# Sensors.net
KiCad netlist of a schematic drawn in Altium Designer
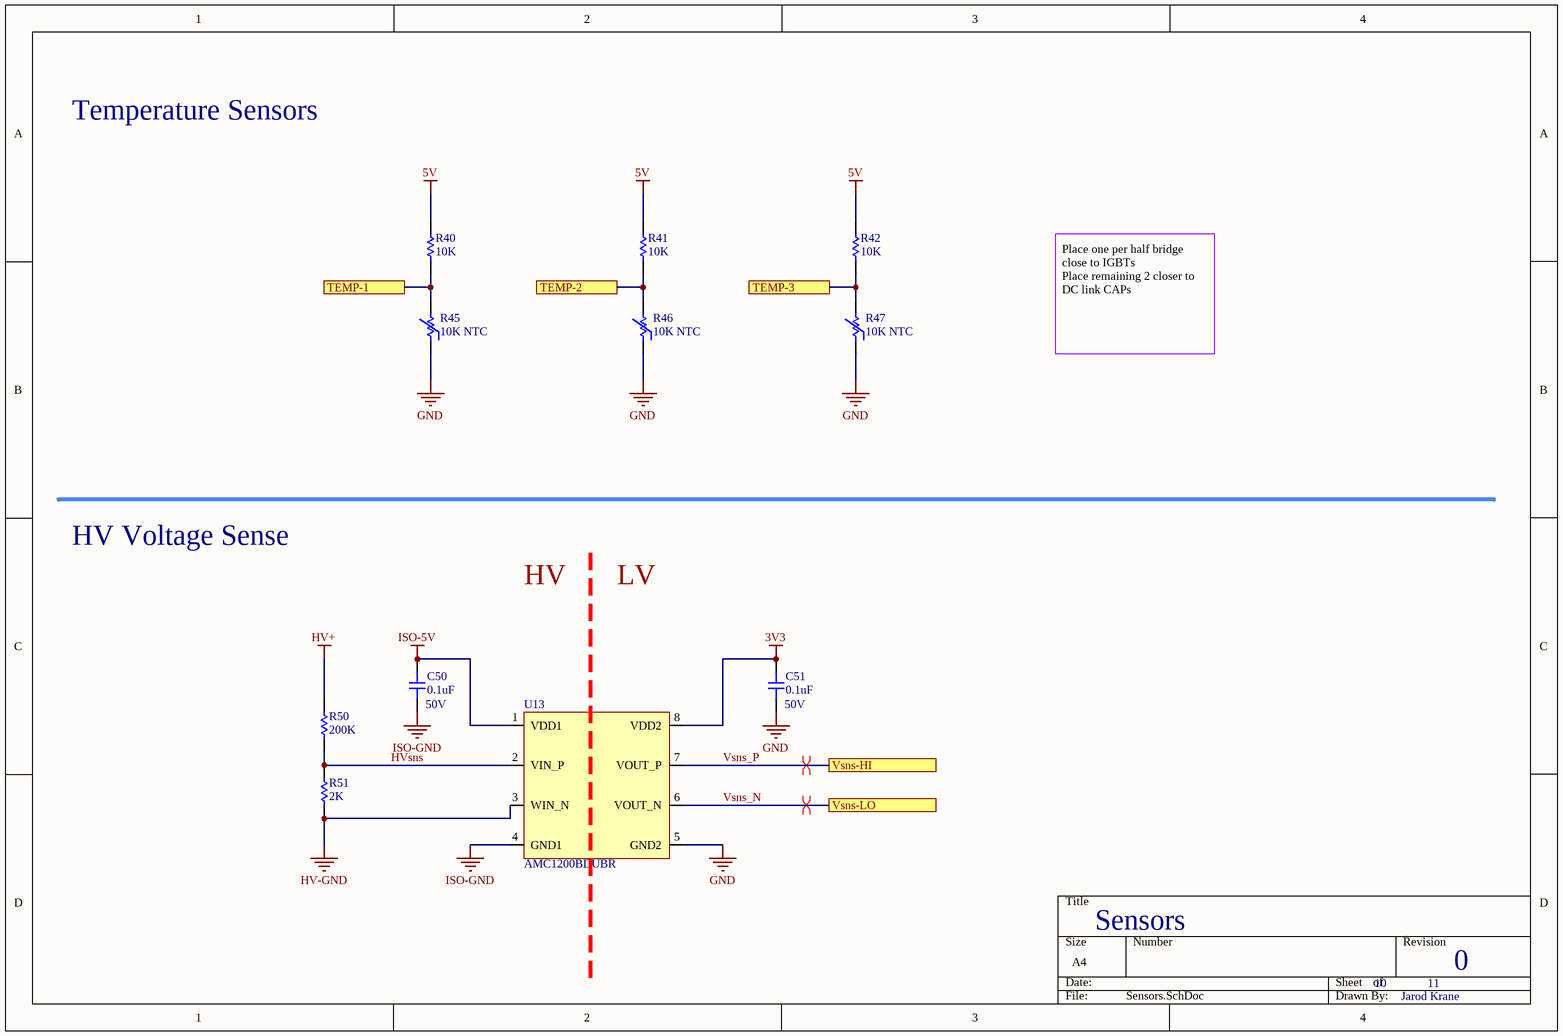
[diagram p0: Sensors.SchDoc]

(export (version "E")
  (design (tool "Eeschema 10.0.6"))
  (components
    (comp (ref "C50")
      (value "0.1uF")
      (footprint "CAP-0805")
      (description "CAP CER 0.1UF 50V Y5V 0805")
      (fields
        (field (name "MANUFACTURER") "KEMET")
        (field (name "MANUFACTURER PART NUMBER") "C0805C104Z5VACTU")
        (field (name "VOLTAGE RATING (DC)") "50V")
      )
      (libsource (lib "InverterSCHLib") (part "0805-0.1uF-50V"))
    )
    (comp (ref "C51")
      (value "0.1uF")
      (footprint "CAP-0805")
      (description "CAP CER 0.1UF 50V Y5V 0805")
      (fields
        (field (name "MANUFACTURER") "KEMET")
        (field (name "MANUFACTURER PART NUMBER") "C0805C104Z5VACTU")
        (field (name "VOLTAGE") "50V")
      )
      (libsource (lib "InverterSCHLib") (part "0805-0.1uF-50V"))
    )
    (comp (ref "R40")
      (value "10K")
      (footprint "RES-0603")
      (description "RES SMD 10K OHM 5% 1/10W 0603")
      (fields
        (field (name "MANUFACTURER") "Yageo")
        (field (name "MANUFACTURER PART NUMBER") "RC0603JR-0710KL")
      )
      (libsource (lib "InverterSCHLib") (part "0603-10KR"))
    )
    (comp (ref "R41")
      (value "10K")
      (footprint "RES-0603")
      (description "RES SMD 10K OHM 5% 1/10W 0603")
      (fields
        (field (name "MANUFACTURER") "Yageo")
        (field (name "MANUFACTURER PART NUMBER") "RC0603JR-0710KL")
      )
      (libsource (lib "InverterSCHLib") (part "0603-10KR"))
    )
    (comp (ref "R42")
      (value "10K")
      (footprint "RES-0603")
      (description "RES SMD 10K OHM 5% 1/10W 0603")
      (fields
        (field (name "MANUFACTURER") "Yageo")
        (field (name "MANUFACTURER PART NUMBER") "RC0603JR-0710KL")
      )
      (libsource (lib "InverterSCHLib") (part "0603-10KR"))
    )
    (comp (ref "R45")
      (value "10K NTC")
      (footprint "RES-0603")
      (description "THERMISTOR NTC 10KOHM 3380K 0603")
      (fields
        (field (name "MANUFACTURER") "Murata")
        (field (name "MANUFACTURER PART NUMBER") "NCP18XH103F03RB")
      )
      (libsource (lib "InverterSCHLib") (part "0603-10K-thermistor"))
    )
    (comp (ref "R46")
      (value "10K NTC")
      (footprint "RES-0603")
      (description "THERMISTOR NTC 10KOHM 3380K 0603")
      (fields
        (field (name "MANUFACTURER") "Murata")
        (field (name "MANUFACTURER PART NUMBER") "NCP18XH103F03RB")
      )
      (libsource (lib "InverterSCHLib") (part "0603-10K-thermistor"))
    )
    (comp (ref "R47")
      (value "10K NTC")
      (footprint "RES-0603")
      (description "THERMISTOR NTC 10KOHM 3380K 0603")
      (fields
        (field (name "MANUFACTURER") "Murata")
        (field (name "MANUFACTURER PART NUMBER") "NCP18XH103F03RB")
      )
      (libsource (lib "InverterSCHLib") (part "0603-10K-thermistor"))
    )
    (comp (ref "R50")
      (value "200K")
      (footprint "RES-0603")
      (description "RES SMD 200K OHM 1% 1/10W 0603")
      (fields
        (field (name "MANUFACTURER") "Yageo")
        (field (name "MANUFACTURER PART NUMBER") "AF0603FR-07200KL")
      )
      (libsource (lib "InverterSCHLib") (part "0603-200KR"))
    )
    (comp (ref "R51")
      (value "2K")
      (footprint "RES-0603")
      (description "RES SMD 2K OHM 1% 1/4W 0603")
      (fields
        (field (name "MANUFACTURER") "Vishay Dale")
        (field (name "MANUFACTURER PART NUMBER") "CRCW06032K00FKEAHP")
      )
      (libsource (lib "InverterSCHLib") (part "0603-2KR"))
    )
    (comp (ref "U13")
      (value "AMC1200BDUBR")
      (footprint "8-SOP")
      (description "IC OPAMP ISOLATION 1 CIRC 8SOP")
      (fields (field (name "MANUFACTURER") "Texas Instruments"))
      (libsource (lib "InverterSCHLib") (part "ISO-OPAMP"))
    )
  )
  (nets
    (net (code "1") (name "/HVsns") (class "Default")
      (node (ref "R50") (pin "1") (pinfunction "1_1") (pintype "passive"))
      (node (ref "R51") (pin "2") (pinfunction "2_2") (pintype "passive"))
      (node (ref "U13") (pin "2") (pinfunction "VIN_P_2") (pintype "passive"))
    )
    (net (code "2") (name "/TEMP-1") (class "Default")
      (node (ref "R40") (pin "1") (pinfunction "1_1") (pintype "passive"))
      (node (ref "R45") (pin "2") (pinfunction "2_2") (pintype "passive"))
    )
    (net (code "3") (name "/TEMP-2") (class "Default")
      (node (ref "R41") (pin "1") (pinfunction "1_1") (pintype "passive"))
      (node (ref "R46") (pin "2") (pinfunction "2_2") (pintype "passive"))
    )
    (net (code "4") (name "/TEMP-3") (class "Default")
      (node (ref "R42") (pin "1") (pinfunction "1_1") (pintype "passive"))
      (node (ref "R47") (pin "2") (pinfunction "2_2") (pintype "passive"))
    )
    (net (code "5") (name "/Vsns_N") (class "Default")
      (node (ref "U13") (pin "6") (pinfunction "VOUT_N_6") (pintype "passive"))
    )
    (net (code "6") (name "/Vsns_P") (class "Default")
      (node (ref "U13") (pin "7") (pinfunction "VOUT_P_7") (pintype "passive"))
    )
    (net (code "7") (name "3V3") (class "Default")
      (node (ref "C51") (pin "2") (pinfunction "2_2") (pintype "passive"))
      (node (ref "U13") (pin "8") (pinfunction "VDD2_8") (pintype "passive"))
    )
    (net (code "8") (name "5V") (class "Default")
      (node (ref "R40") (pin "2") (pinfunction "2_2") (pintype "passive"))
      (node (ref "R41") (pin "2") (pinfunction "2_2") (pintype "passive"))
      (node (ref "R42") (pin "2") (pinfunction "2_2") (pintype "passive"))
    )
    (net (code "9") (name "GND") (class "Default")
      (node (ref "C51") (pin "1") (pinfunction "1_1") (pintype "passive"))
      (node (ref "R45") (pin "1") (pinfunction "1_1") (pintype "passive"))
      (node (ref "R46") (pin "1") (pinfunction "1_1") (pintype "passive"))
      (node (ref "R47") (pin "1") (pinfunction "1_1") (pintype "passive"))
      (node (ref "U13") (pin "5") (pinfunction "GND2_5") (pintype "passive"))
    )
    (net (code "10") (name "HV+") (class "Default")
      (node (ref "R50") (pin "2") (pinfunction "2_2") (pintype "passive"))
    )
    (net (code "11") (name "HV-GND") (class "Default")
      (node (ref "R51") (pin "1") (pinfunction "1_1") (pintype "passive"))
      (node (ref "U13") (pin "3") (pinfunction "WIN_N_3") (pintype "passive"))
    )
    (net (code "12") (name "ISO-5V") (class "Default")
      (node (ref "C50") (pin "2") (pinfunction "2_2") (pintype "passive"))
      (node (ref "U13") (pin "1") (pinfunction "VDD1_1") (pintype "passive"))
    )
    (net (code "13") (name "ISO-GND") (class "Default")
      (node (ref "C50") (pin "1") (pinfunction "1_1") (pintype "passive"))
      (node (ref "U13") (pin "4") (pinfunction "GND1_4") (pintype "passive"))
    )
  )
)
